# MCPv4_eingabe.net
KiCad netlist of a schematic drawn in EAGLE
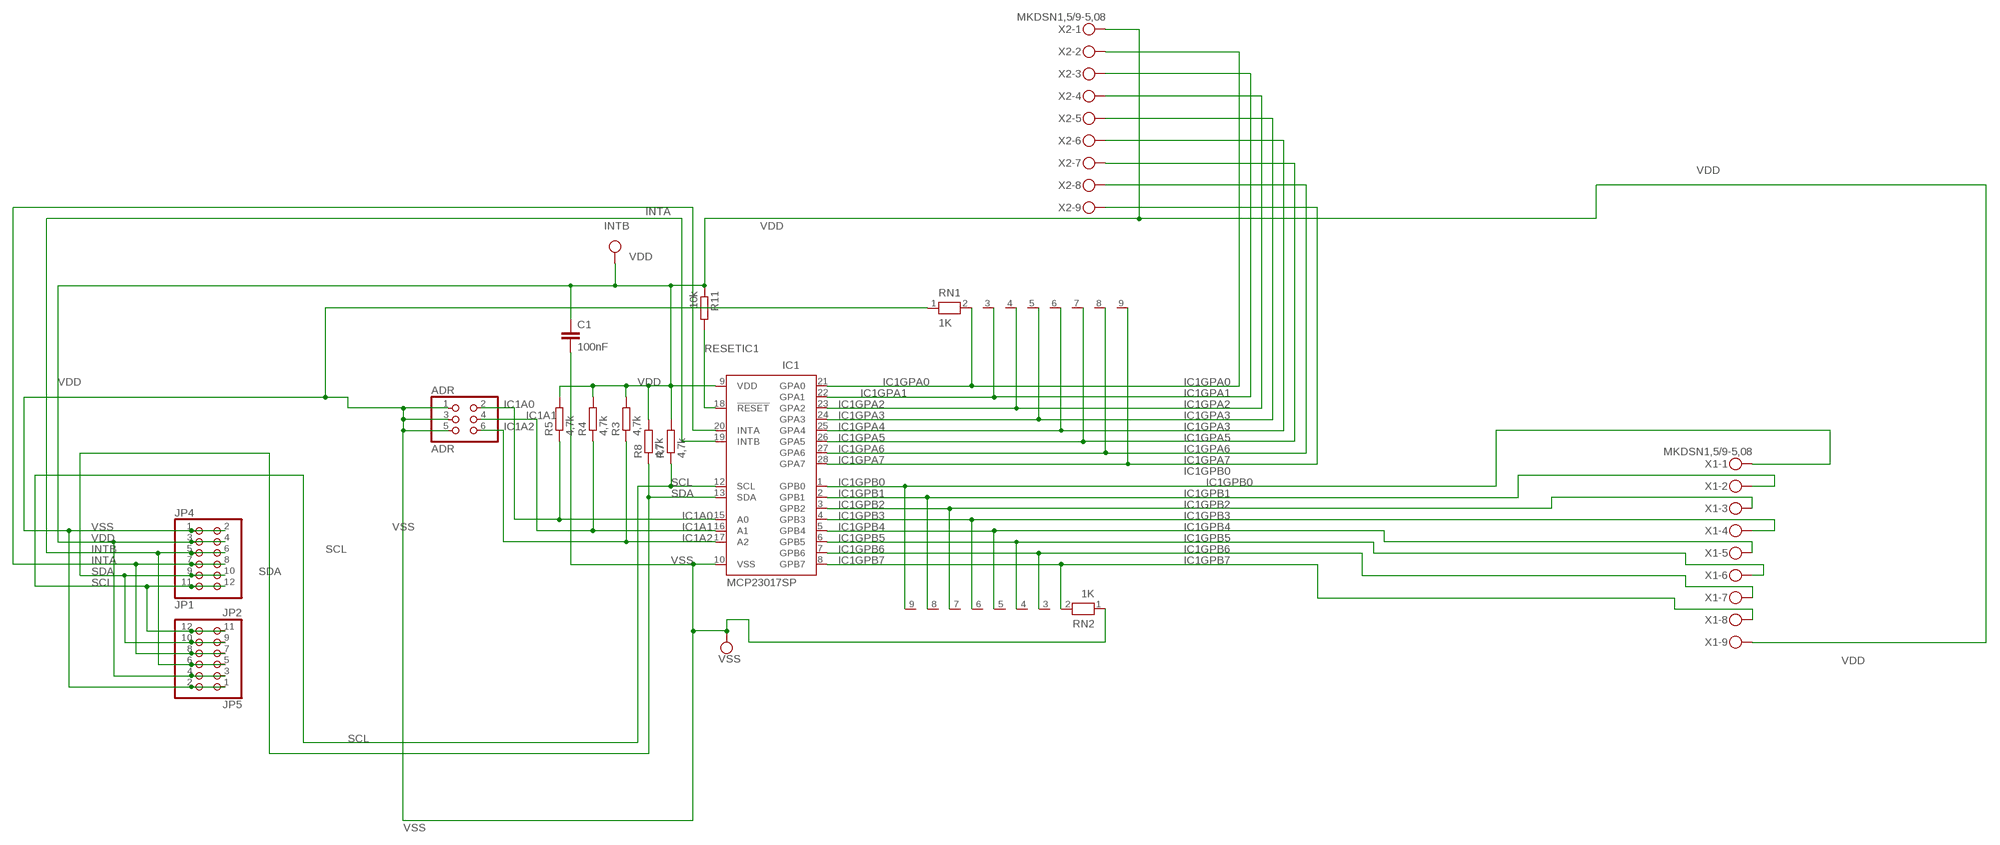
[diagram p0: schematic, sheet 1]

(export (version "E")
  (design (tool "Eeschema 10.0.6"))
  (components
    (comp (ref "ADR")
      (value "ADR")
      (footprint "eagle-import:2X03")
      (libsource (lib "eagle-import") (part "PINHD-2X3"))
    )
    (comp (ref "C1")
      (value "100nF")
      (footprint "eagle-import:C025_050-025X075")
      (libsource (lib "eagle-import") (part "C-EU025_050-025X075"))
    )
    (comp (ref "IC1")
      (value "MCP23017SP")
      (footprint "eagle-import:DIL28-3")
      (fields (field (name "MF") "MICROCHIP") (field (name "MPN") "MCP23017-E/SP"))
      (libsource (lib "eagle-import") (part "MCP23017SP"))
    )
    (comp (ref "JP4")
      (value "JP1")
      (footprint "eagle-import:2X06_90")
      (libsource (lib "eagle-import") (part "PINHD-2X6/90"))
    )
    (comp (ref "JP5")
      (value "JP2")
      (footprint "eagle-import:2X06_90")
      (libsource (lib "eagle-import") (part "PINHD-2X6/90"))
    )
    (comp (ref "R3")
      (value "4,7k")
      (footprint "eagle-import:0204_7")
      (libsource (lib "eagle-import") (part "R-EU_0204/7"))
    )
    (comp (ref "R4")
      (value "4,7k")
      (footprint "eagle-import:0204_7")
      (libsource (lib "eagle-import") (part "R-EU_0204/7"))
    )
    (comp (ref "R5")
      (value "4,7k")
      (footprint "eagle-import:0204_7")
      (libsource (lib "eagle-import") (part "R-EU_0204/7"))
    )
    (comp (ref "R7")
      (value "4,7k")
      (footprint "eagle-import:0204_7")
      (libsource (lib "eagle-import") (part "R-EU_0204/7"))
    )
    (comp (ref "R8")
      (value "4,7k")
      (footprint "eagle-import:0204_7")
      (libsource (lib "eagle-import") (part "R-EU_0204/7"))
    )
    (comp (ref "R11")
      (value "10k")
      (footprint "eagle-import:0204_7")
      (libsource (lib "eagle-import") (part "R-EU_0204/7"))
    )
    (comp (ref "RN1")
      (value "1K")
      (footprint "eagle-import:RN-9")
      (libsource (lib "eagle-import") (part "RN08"))
    )
    (comp (ref "RN2")
      (value "1K")
      (footprint "eagle-import:RN-9")
      (libsource (lib "eagle-import") (part "RN08"))
    )
    (comp (ref "X1")
      (value "MKDSN1,5/9-5,08")
      (footprint "eagle-import:MKDSN1,5_9-5,08")
      (libsource (lib "eagle-import") (part "MKDSN1,5/9-5,08"))
    )
    (comp (ref "X2")
      (value "MKDSN1,5/9-5,08")
      (footprint "eagle-import:MKDSN1,5_9-5,08")
      (libsource (lib "eagle-import") (part "MKDSN1,5/9-5,08"))
    )
  )
  (nets
    (net (code "1") (name "/IC1A0") (class "Default")
      (node (ref "ADR") (pin "2") (pinfunction "2_2") (pintype "passive"))
      (node (ref "IC1") (pin "15") (pinfunction "A0_15") (pintype "input"))
      (node (ref "R5") (pin "1") (pinfunction "1_1") (pintype "passive"))
    )
    (net (code "2") (name "/IC1A1") (class "Default")
      (node (ref "ADR") (pin "4") (pinfunction "4_4") (pintype "passive"))
      (node (ref "IC1") (pin "16") (pinfunction "A1_16") (pintype "input"))
      (node (ref "R4") (pin "1") (pinfunction "1_1") (pintype "passive"))
    )
    (net (code "3") (name "/IC1A2") (class "Default")
      (node (ref "ADR") (pin "6") (pinfunction "6_6") (pintype "passive"))
      (node (ref "IC1") (pin "17") (pinfunction "A2_17") (pintype "input"))
      (node (ref "R3") (pin "1") (pinfunction "1_1") (pintype "passive"))
    )
    (net (code "4") (name "/IC1GPA0") (class "Default")
      (node (ref "IC1") (pin "21") (pinfunction "GPA0_21") (pintype "bidirectional"))
      (node (ref "RN1") (pin "2") (pinfunction "2_2") (pintype "passive"))
      (node (ref "X2") (pin "2") (pinfunction "KL_2") (pintype "passive"))
    )
    (net (code "5") (name "/IC1GPA1") (class "Default")
      (node (ref "IC1") (pin "22") (pinfunction "GPA1_22") (pintype "bidirectional"))
      (node (ref "RN1") (pin "3") (pinfunction "3_3") (pintype "passive"))
      (node (ref "X2") (pin "3") (pinfunction "KL_3") (pintype "passive"))
    )
    (net (code "6") (name "/IC1GPA2") (class "Default")
      (node (ref "IC1") (pin "23") (pinfunction "GPA2_23") (pintype "bidirectional"))
      (node (ref "RN1") (pin "4") (pinfunction "4_4") (pintype "passive"))
      (node (ref "X2") (pin "4") (pinfunction "KL_4") (pintype "passive"))
    )
    (net (code "7") (name "/IC1GPA3") (class "Default")
      (node (ref "IC1") (pin "24") (pinfunction "GPA3_24") (pintype "bidirectional"))
      (node (ref "RN1") (pin "5") (pinfunction "5_5") (pintype "passive"))
      (node (ref "X2") (pin "5") (pinfunction "KL_5") (pintype "passive"))
    )
    (net (code "8") (name "/IC1GPA4") (class "Default")
      (node (ref "IC1") (pin "25") (pinfunction "GPA4_25") (pintype "bidirectional"))
      (node (ref "RN1") (pin "6") (pinfunction "6_6") (pintype "passive"))
      (node (ref "X2") (pin "6") (pinfunction "KL_6") (pintype "passive"))
    )
    (net (code "9") (name "/IC1GPA5") (class "Default")
      (node (ref "IC1") (pin "26") (pinfunction "GPA5_26") (pintype "bidirectional"))
      (node (ref "RN1") (pin "7") (pinfunction "7_7") (pintype "passive"))
      (node (ref "X2") (pin "7") (pinfunction "KL_7") (pintype "passive"))
    )
    (net (code "10") (name "/IC1GPA6") (class "Default")
      (node (ref "IC1") (pin "27") (pinfunction "GPA6_27") (pintype "bidirectional"))
      (node (ref "RN1") (pin "8") (pinfunction "8_8") (pintype "passive"))
      (node (ref "X2") (pin "8") (pinfunction "KL_8") (pintype "passive"))
    )
    (net (code "11") (name "/IC1GPA7") (class "Default")
      (node (ref "IC1") (pin "28") (pinfunction "GPA7_28") (pintype "bidirectional"))
      (node (ref "RN1") (pin "9") (pinfunction "9_9") (pintype "passive"))
      (node (ref "X2") (pin "9") (pinfunction "KL_9") (pintype "passive"))
    )
    (net (code "12") (name "/IC1GPB0") (class "Default")
      (node (ref "IC1") (pin "1") (pinfunction "GPB0_1") (pintype "bidirectional"))
      (node (ref "RN2") (pin "9") (pinfunction "9_9") (pintype "passive"))
      (node (ref "X1") (pin "1") (pinfunction "KL_1") (pintype "passive"))
    )
    (net (code "13") (name "/IC1GPB1") (class "Default")
      (node (ref "IC1") (pin "2") (pinfunction "GPB1_2") (pintype "bidirectional"))
      (node (ref "RN2") (pin "8") (pinfunction "8_8") (pintype "passive"))
      (node (ref "X1") (pin "2") (pinfunction "KL_2") (pintype "passive"))
    )
    (net (code "14") (name "/IC1GPB2") (class "Default")
      (node (ref "IC1") (pin "3") (pinfunction "GPB2_3") (pintype "bidirectional"))
      (node (ref "RN2") (pin "7") (pinfunction "7_7") (pintype "passive"))
      (node (ref "X1") (pin "3") (pinfunction "KL_3") (pintype "passive"))
    )
    (net (code "15") (name "/IC1GPB3") (class "Default")
      (node (ref "IC1") (pin "4") (pinfunction "GPB3_4") (pintype "bidirectional"))
      (node (ref "RN2") (pin "6") (pinfunction "6_6") (pintype "passive"))
      (node (ref "X1") (pin "4") (pinfunction "KL_4") (pintype "passive"))
    )
    (net (code "16") (name "/IC1GPB4") (class "Default")
      (node (ref "IC1") (pin "5") (pinfunction "GPB4_5") (pintype "bidirectional"))
      (node (ref "RN2") (pin "5") (pinfunction "5_5") (pintype "passive"))
      (node (ref "X1") (pin "5") (pinfunction "KL_5") (pintype "passive"))
    )
    (net (code "17") (name "/IC1GPB5") (class "Default")
      (node (ref "IC1") (pin "6") (pinfunction "GPB5_6") (pintype "bidirectional"))
      (node (ref "RN2") (pin "4") (pinfunction "4_4") (pintype "passive"))
      (node (ref "X1") (pin "6") (pinfunction "KL_6") (pintype "passive"))
    )
    (net (code "18") (name "/IC1GPB6") (class "Default")
      (node (ref "IC1") (pin "7") (pinfunction "GPB6_7") (pintype "bidirectional"))
      (node (ref "RN2") (pin "3") (pinfunction "3_3") (pintype "passive"))
      (node (ref "X1") (pin "7") (pinfunction "KL_7") (pintype "passive"))
    )
    (net (code "19") (name "/IC1GPB7") (class "Default")
      (node (ref "IC1") (pin "8") (pinfunction "GPB7_8") (pintype "bidirectional"))
      (node (ref "RN2") (pin "2") (pinfunction "2_2") (pintype "passive"))
      (node (ref "X1") (pin "8") (pinfunction "KL_8") (pintype "passive"))
    )
    (net (code "20") (name "/INTA") (class "Default")
      (node (ref "IC1") (pin "20") (pinfunction "INTA_20") (pintype "output"))
      (node (ref "JP4") (pin "7") (pinfunction "7_7") (pintype "passive"))
      (node (ref "JP4") (pin "8") (pinfunction "8_8") (pintype "passive"))
      (node (ref "JP5") (pin "7") (pinfunction "7_7") (pintype "passive"))
      (node (ref "JP5") (pin "8") (pinfunction "8_8") (pintype "passive"))
    )
    (net (code "21") (name "/INTB") (class "Default")
      (node (ref "IC1") (pin "19") (pinfunction "INTB_19") (pintype "output"))
      (node (ref "JP4") (pin "5") (pinfunction "5_5") (pintype "passive"))
      (node (ref "JP4") (pin "6") (pinfunction "6_6") (pintype "passive"))
      (node (ref "JP5") (pin "5") (pinfunction "5_5") (pintype "passive"))
      (node (ref "JP5") (pin "6") (pinfunction "6_6") (pintype "passive"))
    )
    (net (code "22") (name "/RESETIC1") (class "Default")
      (node (ref "IC1") (pin "18") (pinfunction "~{RESET}_18") (pintype "input"))
      (node (ref "R11") (pin "2") (pinfunction "2_2") (pintype "passive"))
    )
    (net (code "23") (name "/SCL") (class "Default")
      (node (ref "IC1") (pin "12") (pinfunction "SCL_12") (pintype "input"))
      (node (ref "JP4") (pin "11") (pinfunction "11_11") (pintype "passive"))
      (node (ref "JP4") (pin "12") (pinfunction "12_12") (pintype "passive"))
      (node (ref "JP5") (pin "11") (pinfunction "11_11") (pintype "passive"))
      (node (ref "JP5") (pin "12") (pinfunction "12_12") (pintype "passive"))
      (node (ref "R7") (pin "1") (pinfunction "1_1") (pintype "passive"))
    )
    (net (code "24") (name "/SDA") (class "Default")
      (node (ref "IC1") (pin "13") (pinfunction "SDA_13") (pintype "bidirectional"))
      (node (ref "JP4") (pin "10") (pinfunction "10_10") (pintype "passive"))
      (node (ref "JP4") (pin "9") (pinfunction "9_9") (pintype "passive"))
      (node (ref "JP5") (pin "10") (pinfunction "10_10") (pintype "passive"))
      (node (ref "JP5") (pin "9") (pinfunction "9_9") (pintype "passive"))
      (node (ref "R8") (pin "1") (pinfunction "1_1") (pintype "passive"))
    )
    (net (code "25") (name "VDD") (class "Default")
      (node (ref "C1") (pin "1") (pinfunction "1_1") (pintype "passive"))
      (node (ref "IC1") (pin "9") (pinfunction "VDD_9") (pintype "power_in"))
      (node (ref "JP4") (pin "3") (pinfunction "3_3") (pintype "passive"))
      (node (ref "JP4") (pin "4") (pinfunction "4_4") (pintype "passive"))
      (node (ref "JP5") (pin "3") (pinfunction "3_3") (pintype "passive"))
      (node (ref "JP5") (pin "4") (pinfunction "4_4") (pintype "passive"))
      (node (ref "R11") (pin "1") (pinfunction "1_1") (pintype "passive"))
      (node (ref "R3") (pin "2") (pinfunction "2_2") (pintype "passive"))
      (node (ref "R4") (pin "2") (pinfunction "2_2") (pintype "passive"))
      (node (ref "R5") (pin "2") (pinfunction "2_2") (pintype "passive"))
      (node (ref "R7") (pin "2") (pinfunction "2_2") (pintype "passive"))
      (node (ref "R8") (pin "2") (pinfunction "2_2") (pintype "passive"))
      (node (ref "X1") (pin "9") (pinfunction "KL_9") (pintype "passive"))
      (node (ref "X2") (pin "1") (pinfunction "KL_1") (pintype "passive"))
    )
    (net (code "26") (name "VSS") (class "Default")
      (node (ref "ADR") (pin "1") (pinfunction "1_1") (pintype "passive"))
      (node (ref "ADR") (pin "3") (pinfunction "3_3") (pintype "passive"))
      (node (ref "ADR") (pin "5") (pinfunction "5_5") (pintype "passive"))
      (node (ref "C1") (pin "2") (pinfunction "2_2") (pintype "passive"))
      (node (ref "IC1") (pin "10") (pinfunction "VSS_10") (pintype "power_in"))
      (node (ref "JP4") (pin "1") (pinfunction "1_1") (pintype "passive"))
      (node (ref "JP4") (pin "2") (pinfunction "2_2") (pintype "passive"))
      (node (ref "JP5") (pin "1") (pinfunction "1_1") (pintype "passive"))
      (node (ref "JP5") (pin "2") (pinfunction "2_2") (pintype "passive"))
      (node (ref "RN1") (pin "1") (pinfunction "1_1") (pintype "passive"))
      (node (ref "RN2") (pin "1") (pinfunction "1_1") (pintype "passive"))
    )
  )
)
